# ValpoHat-v002.net
KiCad netlist of a schematic drawn in EAGLE
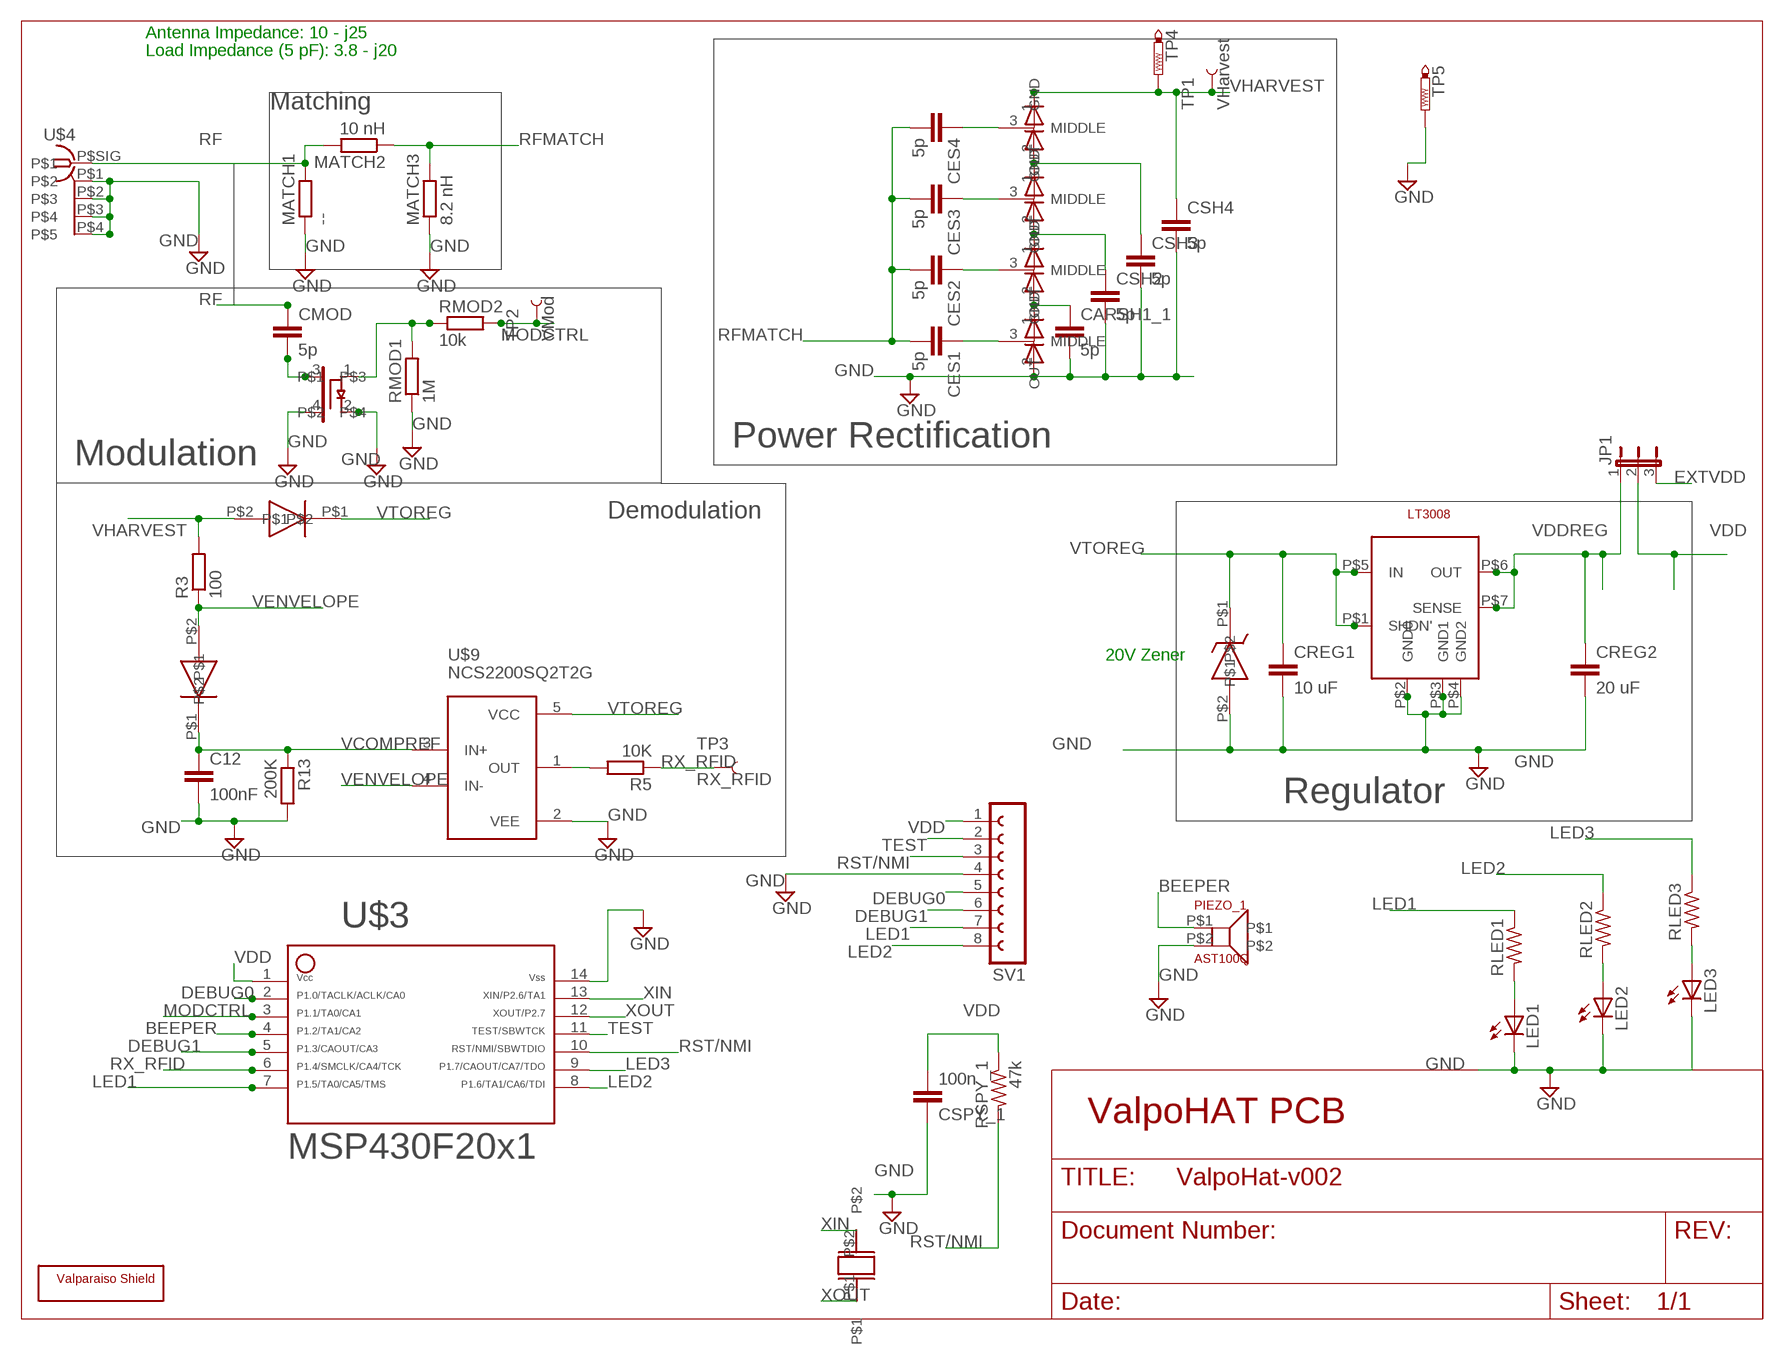
[diagram p0: schematic, sheet 1]

(export (version "E")
  (design (tool "Eeschema 10.0.6"))
  (components
    (comp (ref "C12")
      (value "100nF")
      (footprint "eagle-import:C1206")
      (libsource (lib "eagle-import") (part "C-EUC1206"))
    )
    (comp (ref "CARSH1_1")
      (value "5p")
      (footprint "eagle-import:C0603")
      (libsource (lib "eagle-import") (part "C-EUC0603"))
    )
    (comp (ref "CES1")
      (value "5p")
      (footprint "eagle-import:C0603")
      (libsource (lib "eagle-import") (part "C-EUC0603"))
    )
    (comp (ref "CES2")
      (value "5p")
      (footprint "eagle-import:C0603")
      (libsource (lib "eagle-import") (part "C-EUC0603"))
    )
    (comp (ref "CES3")
      (value "5p")
      (footprint "eagle-import:C0603")
      (libsource (lib "eagle-import") (part "C-EUC0603"))
    )
    (comp (ref "CES4")
      (value "5p")
      (footprint "eagle-import:C0603")
      (libsource (lib "eagle-import") (part "C-EUC0603"))
    )
    (comp (ref "CMOD")
      (value "5p")
      (footprint "eagle-import:C0603")
      (libsource (lib "eagle-import") (part "C-EUC0603"))
    )
    (comp (ref "CREG1")
      (value "10 uF")
      (footprint "eagle-import:C1206")
      (libsource (lib "eagle-import") (part "C-EUC1206"))
    )
    (comp (ref "CREG2")
      (value "20 uF")
      (footprint "eagle-import:C1206")
      (libsource (lib "eagle-import") (part "C-EUC1206"))
    )
    (comp (ref "CSH2")
      (value "5p")
      (footprint "eagle-import:C0603")
      (libsource (lib "eagle-import") (part "C-EUC0603"))
    )
    (comp (ref "CSH3")
      (value "5p")
      (footprint "eagle-import:C0603")
      (libsource (lib "eagle-import") (part "C-EUC0603"))
    )
    (comp (ref "CSH4")
      (value "5p")
      (footprint "eagle-import:C0603")
      (libsource (lib "eagle-import") (part "C-EUC0603"))
    )
    (comp (ref "CSPY_1")
      (value "100n")
      (footprint "eagle-import:C1206")
      (libsource (lib "eagle-import") (part "C-EUC1206"))
    )
    (comp (ref "D1")
      (value "RB751S40T1_EXPAND")
      (footprint "eagle-import:SOD-523_EXPAND")
      (libsource (lib "eagle-import") (part "RB751S40T1_EXPAND"))
    )
    (comp (ref "D2")
      (value "RB751S40T1_EXPAND")
      (footprint "eagle-import:SOD-523_EXPAND")
      (libsource (lib "eagle-import") (part "RB751S40T1_EXPAND"))
    )
    (comp (ref "JP1")
      (value "JP2E")
      (footprint "eagle-import:JP2")
      (libsource (lib "eagle-import") (part "JP2E"))
    )
    (comp (ref "LED1")
      (value "LEDCHIP-LED0603")
      (footprint "eagle-import:CHIP-LED0603")
      (libsource (lib "eagle-import") (part "LEDCHIP-LED0603"))
    )
    (comp (ref "LED2")
      (value "LEDCHIP-LED0603")
      (footprint "eagle-import:CHIP-LED0603")
      (libsource (lib "eagle-import") (part "LEDCHIP-LED0603"))
    )
    (comp (ref "LED3")
      (value "LEDCHIP-LED0603")
      (footprint "eagle-import:CHIP-LED0603")
      (libsource (lib "eagle-import") (part "LEDCHIP-LED0603"))
    )
    (comp (ref "MATCH1")
      (value "--")
      (footprint "eagle-import:R0603")
      (libsource (lib "eagle-import") (part "R-EU_R0603"))
    )
    (comp (ref "MATCH2")
      (value "10 nH")
      (footprint "eagle-import:R0603")
      (libsource (lib "eagle-import") (part "R-EU_R0603"))
    )
    (comp (ref "MATCH3")
      (value "8.2 nH")
      (footprint "eagle-import:R0603")
      (libsource (lib "eagle-import") (part "R-EU_R0603"))
    )
    (comp (ref "PIEZO_1")
      (value "AST100Q")
      (footprint "eagle-import:AST100Q")
      (libsource (lib "eagle-import") (part "AST100Q"))
    )
    (comp (ref "R3")
      (value "100")
      (footprint "eagle-import:R1206")
      (libsource (lib "eagle-import") (part "R-EU_R1206"))
    )
    (comp (ref "R5")
      (value "10K")
      (footprint "eagle-import:R1206")
      (libsource (lib "eagle-import") (part "R-EU_R1206"))
    )
    (comp (ref "R13")
      (value "200K")
      (footprint "eagle-import:R1206")
      (libsource (lib "eagle-import") (part "R-EU_R1206"))
    )
    (comp (ref "RLED1")
      (value "R-US_R1206")
      (footprint "eagle-import:R1206")
      (libsource (lib "eagle-import") (part "R-US_R1206"))
    )
    (comp (ref "RLED2")
      (value "R-US_R1206")
      (footprint "eagle-import:R1206")
      (libsource (lib "eagle-import") (part "R-US_R1206"))
    )
    (comp (ref "RLED3")
      (value "R-US_R1206")
      (footprint "eagle-import:R1206")
      (libsource (lib "eagle-import") (part "R-US_R1206"))
    )
    (comp (ref "RMOD1")
      (value "1M")
      (footprint "eagle-import:R1206")
      (libsource (lib "eagle-import") (part "R-EU_R1206"))
    )
    (comp (ref "RMOD2")
      (value "10k")
      (footprint "eagle-import:R1206")
      (libsource (lib "eagle-import") (part "R-EU_R1206"))
    )
    (comp (ref "RSPY_1")
      (value "47k")
      (footprint "eagle-import:R1206")
      (libsource (lib "eagle-import") (part "R-US_R1206"))
    )
    (comp (ref "SV1")
      (value "FE08-1")
      (footprint "eagle-import:FE08")
      (libsource (lib "eagle-import") (part "FE08-1"))
    )
    (comp (ref "TP1")
      (value "VHarvest")
      (footprint "eagle-import:PAD.03X.03")
      (libsource (lib "eagle-import") (part "TEST-POINT3"))
    )
    (comp (ref "TP2")
      (value "VMod")
      (footprint "eagle-import:PAD.03X.03")
      (libsource (lib "eagle-import") (part "TEST-POINT3"))
    )
    (comp (ref "TP3")
      (value "RX_RFID")
      (footprint "eagle-import:PAD.03X.03")
      (libsource (lib "eagle-import") (part "TEST-POINT3"))
    )
    (comp (ref "TP4")
      (value "TESTPAD_PTR1PAD1-13")
      (footprint "eagle-import:TESTPAD_P1-13")
      (libsource (lib "eagle-import") (part "TESTPAD_PTR1PAD1-13"))
    )
    (comp (ref "TP5")
      (value "TESTPAD_PTR1PAD1-13")
      (footprint "eagle-import:TESTPAD_P1-13")
      (libsource (lib "eagle-import") (part "TESTPAD_PTR1PAD1-13"))
    )
    (comp (ref "U$1")
      (value "BF1108R")
      (footprint "eagle-import:SOT-143R")
      (libsource (lib "eagle-import") (part "BF1108R"))
    )
    (comp (ref "U$2")
      (value "MMSZ4707T1")
      (footprint "eagle-import:SOD-123")
      (libsource (lib "eagle-import") (part "MMSZ4707T1"))
    )
    (comp (ref "U$3")
      (value "F20X1---N14")
      (footprint "eagle-import:N14")
      (libsource (lib "eagle-import") (part "F20X1---N14"))
    )
    (comp (ref "U$4")
      (value "SMA_EDGE_CONN_ALT")
      (footprint "eagle-import:SMA_EDGE_2SIDE")
      (libsource (lib "eagle-import") (part "SMA_EDGE_CONN_ALT"))
    )
    (comp (ref "U$5")
      (value "HSMS2852")
      (footprint "eagle-import:SOT23")
      (libsource (lib "eagle-import") (part "HSMS2852"))
    )
    (comp (ref "U$6")
      (value "HSMS2852")
      (footprint "eagle-import:SOT23")
      (libsource (lib "eagle-import") (part "HSMS2852"))
    )
    (comp (ref "U$7")
      (value "HSMS2852")
      (footprint "eagle-import:SOT23")
      (libsource (lib "eagle-import") (part "HSMS2852"))
    )
    (comp (ref "U$8")
      (value "HSMS2852")
      (footprint "eagle-import:SOT23")
      (libsource (lib "eagle-import") (part "HSMS2852"))
    )
    (comp (ref "U$9")
      (value "NCS2200SQ2T2G")
      (footprint "eagle-import:SC70-5")
      (libsource (lib "eagle-import") (part "NCS2200SQ2T2G"))
    )
    (comp (ref "U$10")
      (value "LT3008-TSOT")
      (footprint "eagle-import:TSOT-23")
      (libsource (lib "eagle-import") (part "LT3008-TSOT"))
    )
    (comp (ref "U$11")
      (value "VALPARAISO-SHIELD")
      (footprint "eagle-import:VUSHIELD-200MIL")
      (libsource (lib "eagle-import") (part "VALPARAISO-SHIELD"))
    )
    (comp (ref "UCRY_1")
      (value "ECX31-BSOLDERABLE")
      (footprint "eagle-import:ECX31-B_EXPAND")
      (libsource (lib "eagle-import") (part "ECX31-BSOLDERABLE"))
    )
  )
  (nets
    (net (code "1") (name "/BEEPER") (class "Default")
      (node (ref "PIEZO_1") (pin "P$1") (pinfunction "P$1_P$1") (pintype "bidirectional"))
      (node (ref "U$3") (pin "4") (pinfunction "4_4") (pintype "bidirectional"))
    )
    (net (code "2") (name "/DEBUG0") (class "Default")
      (node (ref "SV1") (pin "5") (pinfunction "5_5") (pintype "passive"))
      (node (ref "U$3") (pin "2") (pinfunction "2_2") (pintype "bidirectional"))
    )
    (net (code "3") (name "/DEBUG1") (class "Default")
      (node (ref "SV1") (pin "6") (pinfunction "6_6") (pintype "passive"))
      (node (ref "U$3") (pin "5") (pinfunction "5_5") (pintype "bidirectional"))
    )
    (net (code "4") (name "/EXTVDD") (class "Default")
      (node (ref "JP1") (pin "3") (pinfunction "3_3") (pintype "passive"))
    )
    (net (code "5") (name "/LED1") (class "Default")
      (node (ref "RLED1") (pin "1") (pinfunction "1_1") (pintype "passive"))
      (node (ref "SV1") (pin "7") (pinfunction "7_7") (pintype "passive"))
      (node (ref "U$3") (pin "7") (pinfunction "7_7") (pintype "bidirectional"))
    )
    (net (code "6") (name "/LED2") (class "Default")
      (node (ref "RLED2") (pin "1") (pinfunction "1_1") (pintype "passive"))
      (node (ref "SV1") (pin "8") (pinfunction "8_8") (pintype "passive"))
      (node (ref "U$3") (pin "8") (pinfunction "8_8") (pintype "bidirectional"))
    )
    (net (code "7") (name "/LED3") (class "Default")
      (node (ref "RLED3") (pin "1") (pinfunction "1_1") (pintype "passive"))
      (node (ref "U$3") (pin "9") (pinfunction "9_9") (pintype "bidirectional"))
    )
    (net (code "8") (name "/MODCTRL") (class "Default")
      (node (ref "RMOD2") (pin "2") (pinfunction "2_2") (pintype "passive"))
      (node (ref "TP2") (pin "P$1") (pinfunction "1_P$1") (pintype "bidirectional"))
      (node (ref "U$3") (pin "3") (pinfunction "3_3") (pintype "bidirectional"))
    )
    (net (code "9") (name "/RF") (class "Default")
      (node (ref "CMOD") (pin "1") (pinfunction "1_1") (pintype "passive"))
      (node (ref "MATCH1") (pin "2") (pinfunction "2_2") (pintype "passive"))
      (node (ref "MATCH2") (pin "2") (pinfunction "2_2") (pintype "passive"))
      (node (ref "U$4") (pin "P$SIG") (pinfunction "P$1_P$SIG") (pintype "bidirectional"))
    )
    (net (code "10") (name "/RFMATCH") (class "Default")
      (node (ref "CES1") (pin "2") (pinfunction "2_2") (pintype "passive"))
      (node (ref "CES2") (pin "2") (pinfunction "2_2") (pintype "passive"))
      (node (ref "CES3") (pin "2") (pinfunction "2_2") (pintype "passive"))
      (node (ref "CES4") (pin "2") (pinfunction "2_2") (pintype "passive"))
      (node (ref "MATCH2") (pin "1") (pinfunction "1_1") (pintype "passive"))
      (node (ref "MATCH3") (pin "2") (pinfunction "2_2") (pintype "passive"))
    )
    (net (code "11") (name "/RST{slash}NMI") (class "Default")
      (node (ref "RSPY_1") (pin "2") (pinfunction "2_2") (pintype "passive"))
      (node (ref "SV1") (pin "3") (pinfunction "3_3") (pintype "passive"))
      (node (ref "U$3") (pin "10") (pinfunction "10_10") (pintype "bidirectional"))
    )
    (net (code "12") (name "/RX_RFID") (class "Default")
      (node (ref "R5") (pin "1") (pinfunction "1_1") (pintype "passive"))
      (node (ref "TP3") (pin "P$1") (pinfunction "1_P$1") (pintype "bidirectional"))
      (node (ref "U$3") (pin "6") (pinfunction "6_6") (pintype "bidirectional"))
    )
    (net (code "13") (name "/TEST") (class "Default")
      (node (ref "SV1") (pin "2") (pinfunction "2_2") (pintype "passive"))
      (node (ref "U$3") (pin "11") (pinfunction "11_11") (pintype "input"))
    )
    (net (code "14") (name "/VCOMPREF") (class "Default")
      (node (ref "C12") (pin "1") (pinfunction "1_1") (pintype "passive"))
      (node (ref "D2") (pin "P$1") (pinfunction "P$1_P$1") (pintype "bidirectional"))
      (node (ref "R13") (pin "1") (pinfunction "1_1") (pintype "passive"))
      (node (ref "U$9") (pin "3") (pinfunction "IN+_3") (pintype "bidirectional"))
    )
    (net (code "15") (name "/VDD") (class "Default")
      (node (ref "CSPY_1") (pin "2") (pinfunction "2_2") (pintype "passive"))
      (node (ref "JP1") (pin "2") (pinfunction "2_2") (pintype "passive"))
      (node (ref "RSPY_1") (pin "1") (pinfunction "1_1") (pintype "passive"))
      (node (ref "SV1") (pin "1") (pinfunction "1_1") (pintype "passive"))
      (node (ref "U$3") (pin "1") (pinfunction "1_1") (pintype "power_in"))
    )
    (net (code "16") (name "/VDDREG") (class "Default")
      (node (ref "CREG2") (pin "1") (pinfunction "1_1") (pintype "passive"))
      (node (ref "JP1") (pin "1") (pinfunction "1_1") (pintype "passive"))
      (node (ref "U$10") (pin "P$6") (pinfunction "OUT_P$6") (pintype "bidirectional"))
      (node (ref "U$10") (pin "P$7") (pinfunction "SENSE_P$7") (pintype "bidirectional"))
    )
    (net (code "17") (name "/VENVELOPE") (class "Default")
      (node (ref "D2") (pin "P$2") (pinfunction "P$2_P$2") (pintype "bidirectional"))
      (node (ref "R3") (pin "1") (pinfunction "1_1") (pintype "passive"))
      (node (ref "U$9") (pin "4") (pinfunction "IN-_4") (pintype "bidirectional"))
    )
    (net (code "18") (name "/VHARVEST") (class "Default")
      (node (ref "CSH4") (pin "1") (pinfunction "1_1") (pintype "passive"))
      (node (ref "D1") (pin "P$2") (pinfunction "P$2_P$2") (pintype "bidirectional"))
      (node (ref "R3") (pin "2") (pinfunction "2_2") (pintype "passive"))
      (node (ref "TP1") (pin "P$1") (pinfunction "1_P$1") (pintype "bidirectional"))
      (node (ref "TP4") (pin "TP") (pinfunction "TP_TP") (pintype "input"))
      (node (ref "U$8") (pin "1") (pinfunction "OUT_1") (pintype "bidirectional"))
    )
    (net (code "19") (name "/VTOREG") (class "Default")
      (node (ref "CREG1") (pin "1") (pinfunction "1_1") (pintype "passive"))
      (node (ref "D1") (pin "P$1") (pinfunction "P$1_P$1") (pintype "bidirectional"))
      (node (ref "U$10") (pin "P$1") (pinfunction "SHDN'_P$1") (pintype "bidirectional"))
      (node (ref "U$10") (pin "P$5") (pinfunction "IN_P$5") (pintype "bidirectional"))
      (node (ref "U$2") (pin "P$1") (pinfunction "P$1_P$1") (pintype "bidirectional"))
      (node (ref "U$9") (pin "5") (pinfunction "VCC_5") (pintype "bidirectional"))
    )
    (net (code "20") (name "/XIN") (class "Default")
      (node (ref "U$3") (pin "13") (pinfunction "13_13") (pintype "bidirectional"))
      (node (ref "UCRY_1") (pin "P$2") (pinfunction "P$2_P$2") (pintype "bidirectional"))
    )
    (net (code "21") (name "/XOUT") (class "Default")
      (node (ref "U$3") (pin "12") (pinfunction "12_12") (pintype "bidirectional"))
      (node (ref "UCRY_1") (pin "P$1") (pinfunction "P$1_P$1") (pintype "bidirectional"))
    )
    (net (code "22") (name "GND") (class "Default")
      (node (ref "C12") (pin "2") (pinfunction "2_2") (pintype "passive"))
      (node (ref "CARSH1_1") (pin "2") (pinfunction "2_2") (pintype "passive"))
      (node (ref "CREG1") (pin "2") (pinfunction "2_2") (pintype "passive"))
      (node (ref "CREG2") (pin "2") (pinfunction "2_2") (pintype "passive"))
      (node (ref "CSH2") (pin "2") (pinfunction "2_2") (pintype "passive"))
      (node (ref "CSH3") (pin "2") (pinfunction "2_2") (pintype "passive"))
      (node (ref "CSH4") (pin "2") (pinfunction "2_2") (pintype "passive"))
      (node (ref "CSPY_1") (pin "1") (pinfunction "1_1") (pintype "passive"))
      (node (ref "LED1") (pin "C") (pinfunction "C_C") (pintype "passive"))
      (node (ref "LED2") (pin "C") (pinfunction "C_C") (pintype "passive"))
      (node (ref "LED3") (pin "C") (pinfunction "C_C") (pintype "passive"))
      (node (ref "MATCH1") (pin "1") (pinfunction "1_1") (pintype "passive"))
      (node (ref "MATCH3") (pin "1") (pinfunction "1_1") (pintype "passive"))
      (node (ref "PIEZO_1") (pin "P$2") (pinfunction "P$2_P$2") (pintype "bidirectional"))
      (node (ref "R13") (pin "2") (pinfunction "2_2") (pintype "passive"))
      (node (ref "RMOD1") (pin "1") (pinfunction "1_1") (pintype "passive"))
      (node (ref "SV1") (pin "4") (pinfunction "4_4") (pintype "passive"))
      (node (ref "TP5") (pin "TP") (pinfunction "TP_TP") (pintype "input"))
      (node (ref "U$1") (pin "2") (pinfunction "P$2_2") (pintype "bidirectional"))
      (node (ref "U$1") (pin "4") (pinfunction "P$4_4") (pintype "bidirectional"))
      (node (ref "U$10") (pin "P$2") (pinfunction "GND0_P$2") (pintype "power_in"))
      (node (ref "U$10") (pin "P$3") (pinfunction "GND1_P$3") (pintype "power_in"))
      (node (ref "U$10") (pin "P$4") (pinfunction "GND2_P$4") (pintype "power_in"))
      (node (ref "U$2") (pin "P$2") (pinfunction "P$2_P$2") (pintype "bidirectional"))
      (node (ref "U$3") (pin "14") (pinfunction "14_14") (pintype "power_in"))
      (node (ref "U$4") (pin "P$1") (pinfunction "P$2_P$1") (pintype "power_in"))
      (node (ref "U$4") (pin "P$2") (pinfunction "P$3_P$2") (pintype "power_in"))
      (node (ref "U$4") (pin "P$3") (pinfunction "P$4_P$3") (pintype "power_in"))
      (node (ref "U$4") (pin "P$4") (pinfunction "P$5_P$4") (pintype "power_in"))
      (node (ref "U$5") (pin "2") (pinfunction "GND_2") (pintype "bidirectional"))
      (node (ref "U$9") (pin "2") (pinfunction "VEE_2") (pintype "bidirectional"))
    )
    (net (code "23") (name "Net-(LED1-PadA)") (class "Default")
      (node (ref "LED1") (pin "A") (pinfunction "A_A") (pintype "passive"))
      (node (ref "RLED1") (pin "2") (pinfunction "2_2") (pintype "passive"))
    )
    (net (code "24") (name "Net-(LED2-PadA)") (class "Default")
      (node (ref "LED2") (pin "A") (pinfunction "A_A") (pintype "passive"))
      (node (ref "RLED2") (pin "2") (pinfunction "2_2") (pintype "passive"))
    )
    (net (code "25") (name "Net-(LED3-PadA)") (class "Default")
      (node (ref "LED3") (pin "A") (pinfunction "A_A") (pintype "passive"))
      (node (ref "RLED3") (pin "2") (pinfunction "2_2") (pintype "passive"))
    )
    (net (code "26") (name "Net-(U$1-P$1)") (class "Default")
      (node (ref "RMOD1") (pin "2") (pinfunction "2_2") (pintype "passive"))
      (node (ref "RMOD2") (pin "1") (pinfunction "1_1") (pintype "passive"))
      (node (ref "U$1") (pin "1") (pinfunction "P$1_1") (pintype "bidirectional"))
    )
    (net (code "27") (name "Net-(U$1-P$3)") (class "Default")
      (node (ref "CMOD") (pin "2") (pinfunction "2_2") (pintype "passive"))
      (node (ref "U$1") (pin "3") (pinfunction "P$3_3") (pintype "bidirectional"))
    )
    (net (code "28") (name "Net-(U$5-MIDDLE)") (class "Default")
      (node (ref "CES1") (pin "1") (pinfunction "1_1") (pintype "passive"))
      (node (ref "U$5") (pin "3") (pinfunction "MIDDLE_3") (pintype "bidirectional"))
    )
    (net (code "29") (name "Net-(U$5-OUT)") (class "Default")
      (node (ref "CARSH1_1") (pin "1") (pinfunction "1_1") (pintype "passive"))
      (node (ref "U$5") (pin "1") (pinfunction "OUT_1") (pintype "bidirectional"))
      (node (ref "U$6") (pin "2") (pinfunction "GND_2") (pintype "bidirectional"))
    )
    (net (code "30") (name "Net-(U$6-MIDDLE)") (class "Default")
      (node (ref "CES2") (pin "1") (pinfunction "1_1") (pintype "passive"))
      (node (ref "U$6") (pin "3") (pinfunction "MIDDLE_3") (pintype "bidirectional"))
    )
    (net (code "31") (name "Net-(U$6-OUT)") (class "Default")
      (node (ref "CSH2") (pin "1") (pinfunction "1_1") (pintype "passive"))
      (node (ref "U$6") (pin "1") (pinfunction "OUT_1") (pintype "bidirectional"))
      (node (ref "U$7") (pin "2") (pinfunction "GND_2") (pintype "bidirectional"))
    )
    (net (code "32") (name "Net-(U$7-MIDDLE)") (class "Default")
      (node (ref "CES3") (pin "1") (pinfunction "1_1") (pintype "passive"))
      (node (ref "U$7") (pin "3") (pinfunction "MIDDLE_3") (pintype "bidirectional"))
    )
    (net (code "33") (name "Net-(U$7-OUT)") (class "Default")
      (node (ref "CSH3") (pin "1") (pinfunction "1_1") (pintype "passive"))
      (node (ref "U$7") (pin "1") (pinfunction "OUT_1") (pintype "bidirectional"))
      (node (ref "U$8") (pin "2") (pinfunction "GND_2") (pintype "bidirectional"))
    )
    (net (code "34") (name "Net-(U$8-MIDDLE)") (class "Default")
      (node (ref "CES4") (pin "1") (pinfunction "1_1") (pintype "passive"))
      (node (ref "U$8") (pin "3") (pinfunction "MIDDLE_3") (pintype "bidirectional"))
    )
    (net (code "35") (name "Net-(U$9-OUT)") (class "Default")
      (node (ref "R5") (pin "2") (pinfunction "2_2") (pintype "passive"))
      (node (ref "U$9") (pin "1") (pinfunction "OUT_1") (pintype "bidirectional"))
    )
  )
)
